# SCHEM_PRACTICE.net
KiCad netlist of a schematic drawn in Altium Designer
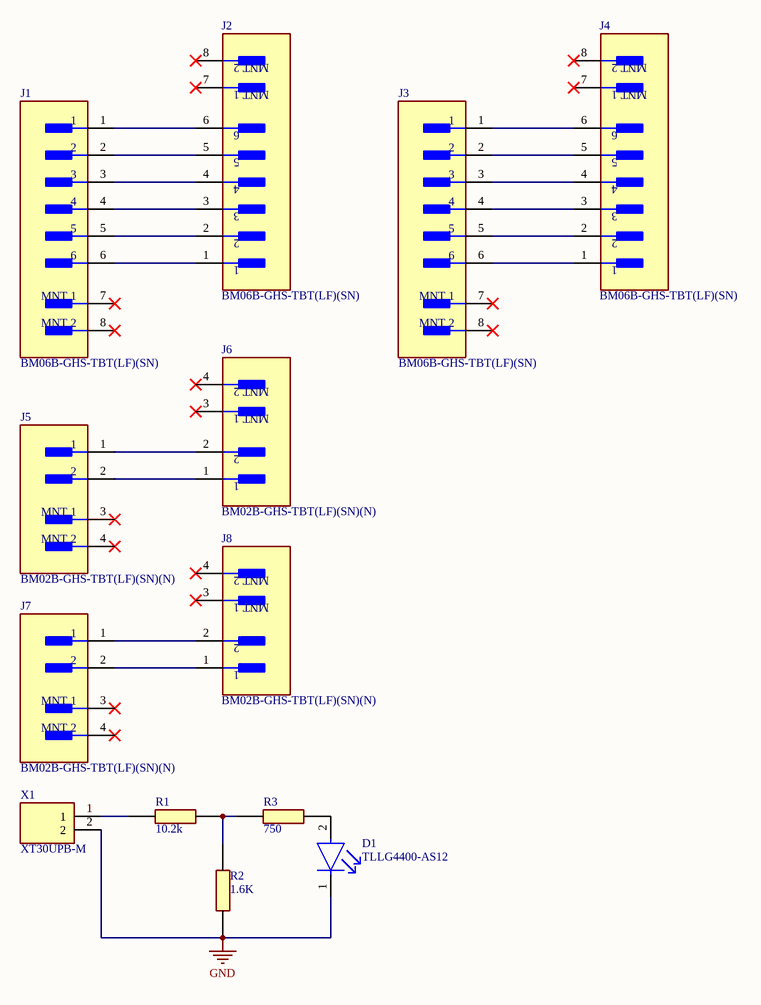
[diagram p0: SCHEM_PRACTICE.SchDoc]

(export (version "E")
  (design (tool "Eeschema 10.0.6"))
  (components
    (comp (ref "D1")
      (value "TLLG4400-AS12")
      (footprint "FP-6_544-5255_01-4-MFG")
      (description "LED GREEN DIFFUSED T-1 T/H")
      (libsource (lib "Altium Content Vault") (part "8706943c75ba83719d021d2fdc84c58"))
    )
    (comp (ref "J1")
      (value "BM06B-GHS-TBT(LF)(SN)")
      (footprint "FP-BM06B-GHS-TBT_LF_SN-MFG")
      (description "CONN HEADER SMD 6POS 1.25MM")
      (libsource (lib "") (part "ed24c53d9ba001d1a2a686240a95171_1"))
    )
    (comp (ref "J2")
      (value "BM06B-GHS-TBT(LF)(SN)")
      (footprint "FP-BM06B-GHS-TBT_LF_SN-MFG")
      (description "CONN HEADER SMD 6POS 1.25MM")
      (libsource (lib "Altium Content Vault") (part "ed24c53d9ba001d1a2a686240a95171"))
    )
    (comp (ref "J3")
      (value "BM06B-GHS-TBT(LF)(SN)")
      (footprint "FP-BM06B-GHS-TBT_LF_SN-MFG")
      (description "CONN HEADER SMD 6POS 1.25MM")
      (libsource (lib "") (part "ed24c53d9ba001d1a2a686240a95171_1"))
    )
    (comp (ref "J4")
      (value "BM06B-GHS-TBT(LF)(SN)")
      (footprint "FP-BM06B-GHS-TBT_LF_SN-MFG")
      (description "CONN HEADER SMD 6POS 1.25MM")
      (libsource (lib "Altium Content Vault") (part "ed24c53d9ba001d1a2a686240a95171"))
    )
    (comp (ref "J5")
      (value "BM02B-GHS-TBT(LF)(SN)(N)")
      (footprint "FP-BM02B-GHS-TBT_LF_SN-MFG")
      (description "CONN HEADER SMD 2POS 1.25MM")
      (libsource (lib "Altium Content Vault") (part "e34efe21362d63d7198b5d2c73e37bd"))
    )
    (comp (ref "J6")
      (value "BM02B-GHS-TBT(LF)(SN)(N)")
      (footprint "FP-BM02B-GHS-TBT_LF_SN-MFG")
      (description "CONN HEADER SMD 2POS 1.25MM")
      (libsource (lib "") (part "e34efe21362d63d7198b5d2c73e37bd_1"))
    )
    (comp (ref "J7")
      (value "BM02B-GHS-TBT(LF)(SN)(N)")
      (footprint "FP-BM02B-GHS-TBT_LF_SN-MFG")
      (description "CONN HEADER SMD 2POS 1.25MM")
      (libsource (lib "Altium Content Vault") (part "e34efe21362d63d7198b5d2c73e37bd"))
    )
    (comp (ref "J8")
      (value "BM02B-GHS-TBT(LF)(SN)(N)")
      (footprint "FP-BM02B-GHS-TBT_LF_SN-MFG")
      (description "CONN HEADER SMD 2POS 1.25MM")
      (libsource (lib "") (part "e34efe21362d63d7198b5d2c73e37bd_1"))
    )
    (comp (ref "R1")
      (value "10.2k")
      (footprint "RESC2012X50N")
      (description "Resistor")
      (fields
        (field (name "MANUFACTURER_PART_NUMBER") "CRCW080510K2FKEA")
        (field (name "MOUSER PART NUMBER") "71-CRCW0805-10.2K-E3")
      )
      (libsource (lib "Symbol_library") (part "CRCW080510K2FKEA"))
    )
    (comp (ref "R2")
      (value "1.6K")
      (footprint "RESC2012X60N")
      (description "Resistor")
      (fields
        (field (name "MANUFACTURER_PART_NUMBER") "CRCW08051K60FKEAC")
        (field (name "MOUSER PART NUMBER") "71-CRCW08051K60FKEAC")
      )
      (libsource (lib "Symbol_library") (part "CRCW08051K60FKEAC"))
    )
    (comp (ref "R3")
      (value "750")
      (footprint "RESC2012X60N")
      (description "Resistor")
      (fields
        (field (name "MANUFACTURER_PART_NUMBER") "CRCW0805750RFKEAHP")
        (field (name "MOUSER PART NUMBER") "71-CRCW0805750RFKEAH")
      )
      (libsource (lib "Symbol_library") (part "CRCW0805750RFKEAHP"))
    )
    (comp (ref "X1")
      (value "XT30UPB-M")
      (footprint "SHDR2W160P0X500_1X2_1020X520X1070P")
      (description "Connector")
      (libsource (lib "Symbol_library") (part "XT30UPB-M"))
    )
  )
  (nets
    (net (code "1") (name "GND") (class "Default")
      (node (ref "D1") (pin "1") (pinfunction "C_1") (pintype "passive"))
      (node (ref "R2") (pin "1") (pinfunction "1_1") (pintype "passive"))
      (node (ref "X1") (pin "2") (pinfunction "2_2") (pintype "passive"))
    )
    (net (code "2") (name "Net-(D1-A)") (class "Default")
      (node (ref "D1") (pin "2") (pinfunction "A_2") (pintype "passive"))
      (node (ref "R3") (pin "2") (pinfunction "2_2") (pintype "passive"))
    )
    (net (code "3") (name "Net-(J1-Pad1)") (class "Default")
      (node (ref "J1") (pin "1") (pinfunction "1_1") (pintype "passive"))
      (node (ref "J2") (pin "6") (pinfunction "6_6") (pintype "passive"))
    )
    (net (code "4") (name "Net-(J1-Pad2)") (class "Default")
      (node (ref "J1") (pin "2") (pinfunction "2_2") (pintype "passive"))
      (node (ref "J2") (pin "5") (pinfunction "5_5") (pintype "passive"))
    )
    (net (code "5") (name "Net-(J1-Pad3)") (class "Default")
      (node (ref "J1") (pin "3") (pinfunction "3_3") (pintype "passive"))
      (node (ref "J2") (pin "4") (pinfunction "4_4") (pintype "passive"))
    )
    (net (code "6") (name "Net-(J1-Pad4)") (class "Default")
      (node (ref "J1") (pin "4") (pinfunction "4_4") (pintype "passive"))
      (node (ref "J2") (pin "3") (pinfunction "3_3") (pintype "passive"))
    )
    (net (code "7") (name "Net-(J1-Pad5)") (class "Default")
      (node (ref "J1") (pin "5") (pinfunction "5_5") (pintype "passive"))
      (node (ref "J2") (pin "2") (pinfunction "2_2") (pintype "passive"))
    )
    (net (code "8") (name "Net-(J1-Pad6)") (class "Default")
      (node (ref "J1") (pin "6") (pinfunction "6_6") (pintype "passive"))
      (node (ref "J2") (pin "1") (pinfunction "1_1") (pintype "passive"))
    )
    (net (code "9") (name "Net-(J3-Pad1)") (class "Default")
      (node (ref "J3") (pin "1") (pinfunction "1_1") (pintype "passive"))
      (node (ref "J4") (pin "6") (pinfunction "6_6") (pintype "passive"))
    )
    (net (code "10") (name "Net-(J3-Pad2)") (class "Default")
      (node (ref "J3") (pin "2") (pinfunction "2_2") (pintype "passive"))
      (node (ref "J4") (pin "5") (pinfunction "5_5") (pintype "passive"))
    )
    (net (code "11") (name "Net-(J3-Pad3)") (class "Default")
      (node (ref "J3") (pin "3") (pinfunction "3_3") (pintype "passive"))
      (node (ref "J4") (pin "4") (pinfunction "4_4") (pintype "passive"))
    )
    (net (code "12") (name "Net-(J3-Pad4)") (class "Default")
      (node (ref "J3") (pin "4") (pinfunction "4_4") (pintype "passive"))
      (node (ref "J4") (pin "3") (pinfunction "3_3") (pintype "passive"))
    )
    (net (code "13") (name "Net-(J3-Pad5)") (class "Default")
      (node (ref "J3") (pin "5") (pinfunction "5_5") (pintype "passive"))
      (node (ref "J4") (pin "2") (pinfunction "2_2") (pintype "passive"))
    )
    (net (code "14") (name "Net-(J3-Pad6)") (class "Default")
      (node (ref "J3") (pin "6") (pinfunction "6_6") (pintype "passive"))
      (node (ref "J4") (pin "1") (pinfunction "1_1") (pintype "passive"))
    )
    (net (code "15") (name "Net-(J5-Pad1)") (class "Default")
      (node (ref "J5") (pin "1") (pinfunction "1_1") (pintype "passive"))
      (node (ref "J6") (pin "2") (pinfunction "2_2") (pintype "passive"))
    )
    (net (code "16") (name "Net-(J5-Pad2)") (class "Default")
      (node (ref "J5") (pin "2") (pinfunction "2_2") (pintype "passive"))
      (node (ref "J6") (pin "1") (pinfunction "1_1") (pintype "passive"))
    )
    (net (code "17") (name "Net-(J7-Pad1)") (class "Default")
      (node (ref "J7") (pin "1") (pinfunction "1_1") (pintype "passive"))
      (node (ref "J8") (pin "2") (pinfunction "2_2") (pintype "passive"))
    )
    (net (code "18") (name "Net-(J7-Pad2)") (class "Default")
      (node (ref "J7") (pin "2") (pinfunction "2_2") (pintype "passive"))
      (node (ref "J8") (pin "1") (pinfunction "1_1") (pintype "passive"))
    )
    (net (code "19") (name "Net-(R1-Pad1)") (class "Default")
      (node (ref "R1") (pin "1") (pinfunction "1_1") (pintype "passive"))
      (node (ref "X1") (pin "1") (pinfunction "1_1") (pintype "passive"))
    )
    (net (code "20") (name "Net-(R1-Pad2)") (class "Default")
      (node (ref "R1") (pin "2") (pinfunction "2_2") (pintype "passive"))
      (node (ref "R2") (pin "2") (pinfunction "2_2") (pintype "passive"))
      (node (ref "R3") (pin "1") (pinfunction "1_1") (pintype "passive"))
    )
    (net (code "21") (name "unconnected-(J1-MNT_1-Pad7)") (class "Default")
      (node (ref "J1") (pin "7") (pinfunction "MNT_1_7") (pintype "passive+no_connect"))
    )
    (net (code "22") (name "unconnected-(J1-MNT_2-Pad8)") (class "Default")
      (node (ref "J1") (pin "8") (pinfunction "MNT_2_8") (pintype "passive+no_connect"))
    )
    (net (code "23") (name "unconnected-(J2-MNT_1-Pad7)") (class "Default")
      (node (ref "J2") (pin "7") (pinfunction "MNT_1_7") (pintype "passive+no_connect"))
    )
    (net (code "24") (name "unconnected-(J2-MNT_2-Pad8)") (class "Default")
      (node (ref "J2") (pin "8") (pinfunction "MNT_2_8") (pintype "passive+no_connect"))
    )
    (net (code "25") (name "unconnected-(J3-MNT_1-Pad7)") (class "Default")
      (node (ref "J3") (pin "7") (pinfunction "MNT_1_7") (pintype "passive+no_connect"))
    )
    (net (code "26") (name "unconnected-(J3-MNT_2-Pad8)") (class "Default")
      (node (ref "J3") (pin "8") (pinfunction "MNT_2_8") (pintype "passive+no_connect"))
    )
    (net (code "27") (name "unconnected-(J4-MNT_1-Pad7)") (class "Default")
      (node (ref "J4") (pin "7") (pinfunction "MNT_1_7") (pintype "passive+no_connect"))
    )
    (net (code "28") (name "unconnected-(J4-MNT_2-Pad8)") (class "Default")
      (node (ref "J4") (pin "8") (pinfunction "MNT_2_8") (pintype "passive+no_connect"))
    )
    (net (code "29") (name "unconnected-(J5-MNT_1-Pad3)") (class "Default")
      (node (ref "J5") (pin "3") (pinfunction "MNT_1_3") (pintype "passive+no_connect"))
    )
    (net (code "30") (name "unconnected-(J5-MNT_2-Pad4)") (class "Default")
      (node (ref "J5") (pin "4") (pinfunction "MNT_2_4") (pintype "passive+no_connect"))
    )
    (net (code "31") (name "unconnected-(J6-MNT_1-Pad3)") (class "Default")
      (node (ref "J6") (pin "3") (pinfunction "MNT_1_3") (pintype "passive+no_connect"))
    )
    (net (code "32") (name "unconnected-(J6-MNT_2-Pad4)") (class "Default")
      (node (ref "J6") (pin "4") (pinfunction "MNT_2_4") (pintype "passive+no_connect"))
    )
    (net (code "33") (name "unconnected-(J7-MNT_1-Pad3)") (class "Default")
      (node (ref "J7") (pin "3") (pinfunction "MNT_1_3") (pintype "passive+no_connect"))
    )
    (net (code "34") (name "unconnected-(J7-MNT_2-Pad4)") (class "Default")
      (node (ref "J7") (pin "4") (pinfunction "MNT_2_4") (pintype "passive+no_connect"))
    )
    (net (code "35") (name "unconnected-(J8-MNT_1-Pad3)") (class "Default")
      (node (ref "J8") (pin "3") (pinfunction "MNT_1_3") (pintype "passive+no_connect"))
    )
    (net (code "36") (name "unconnected-(J8-MNT_2-Pad4)") (class "Default")
      (node (ref "J8") (pin "4") (pinfunction "MNT_2_4") (pintype "passive+no_connect"))
    )
  )
)
